# SCH_NFC-Business-Card_new_2024-07-29.net
KiCad netlist of a schematic drawn in EasyEDA
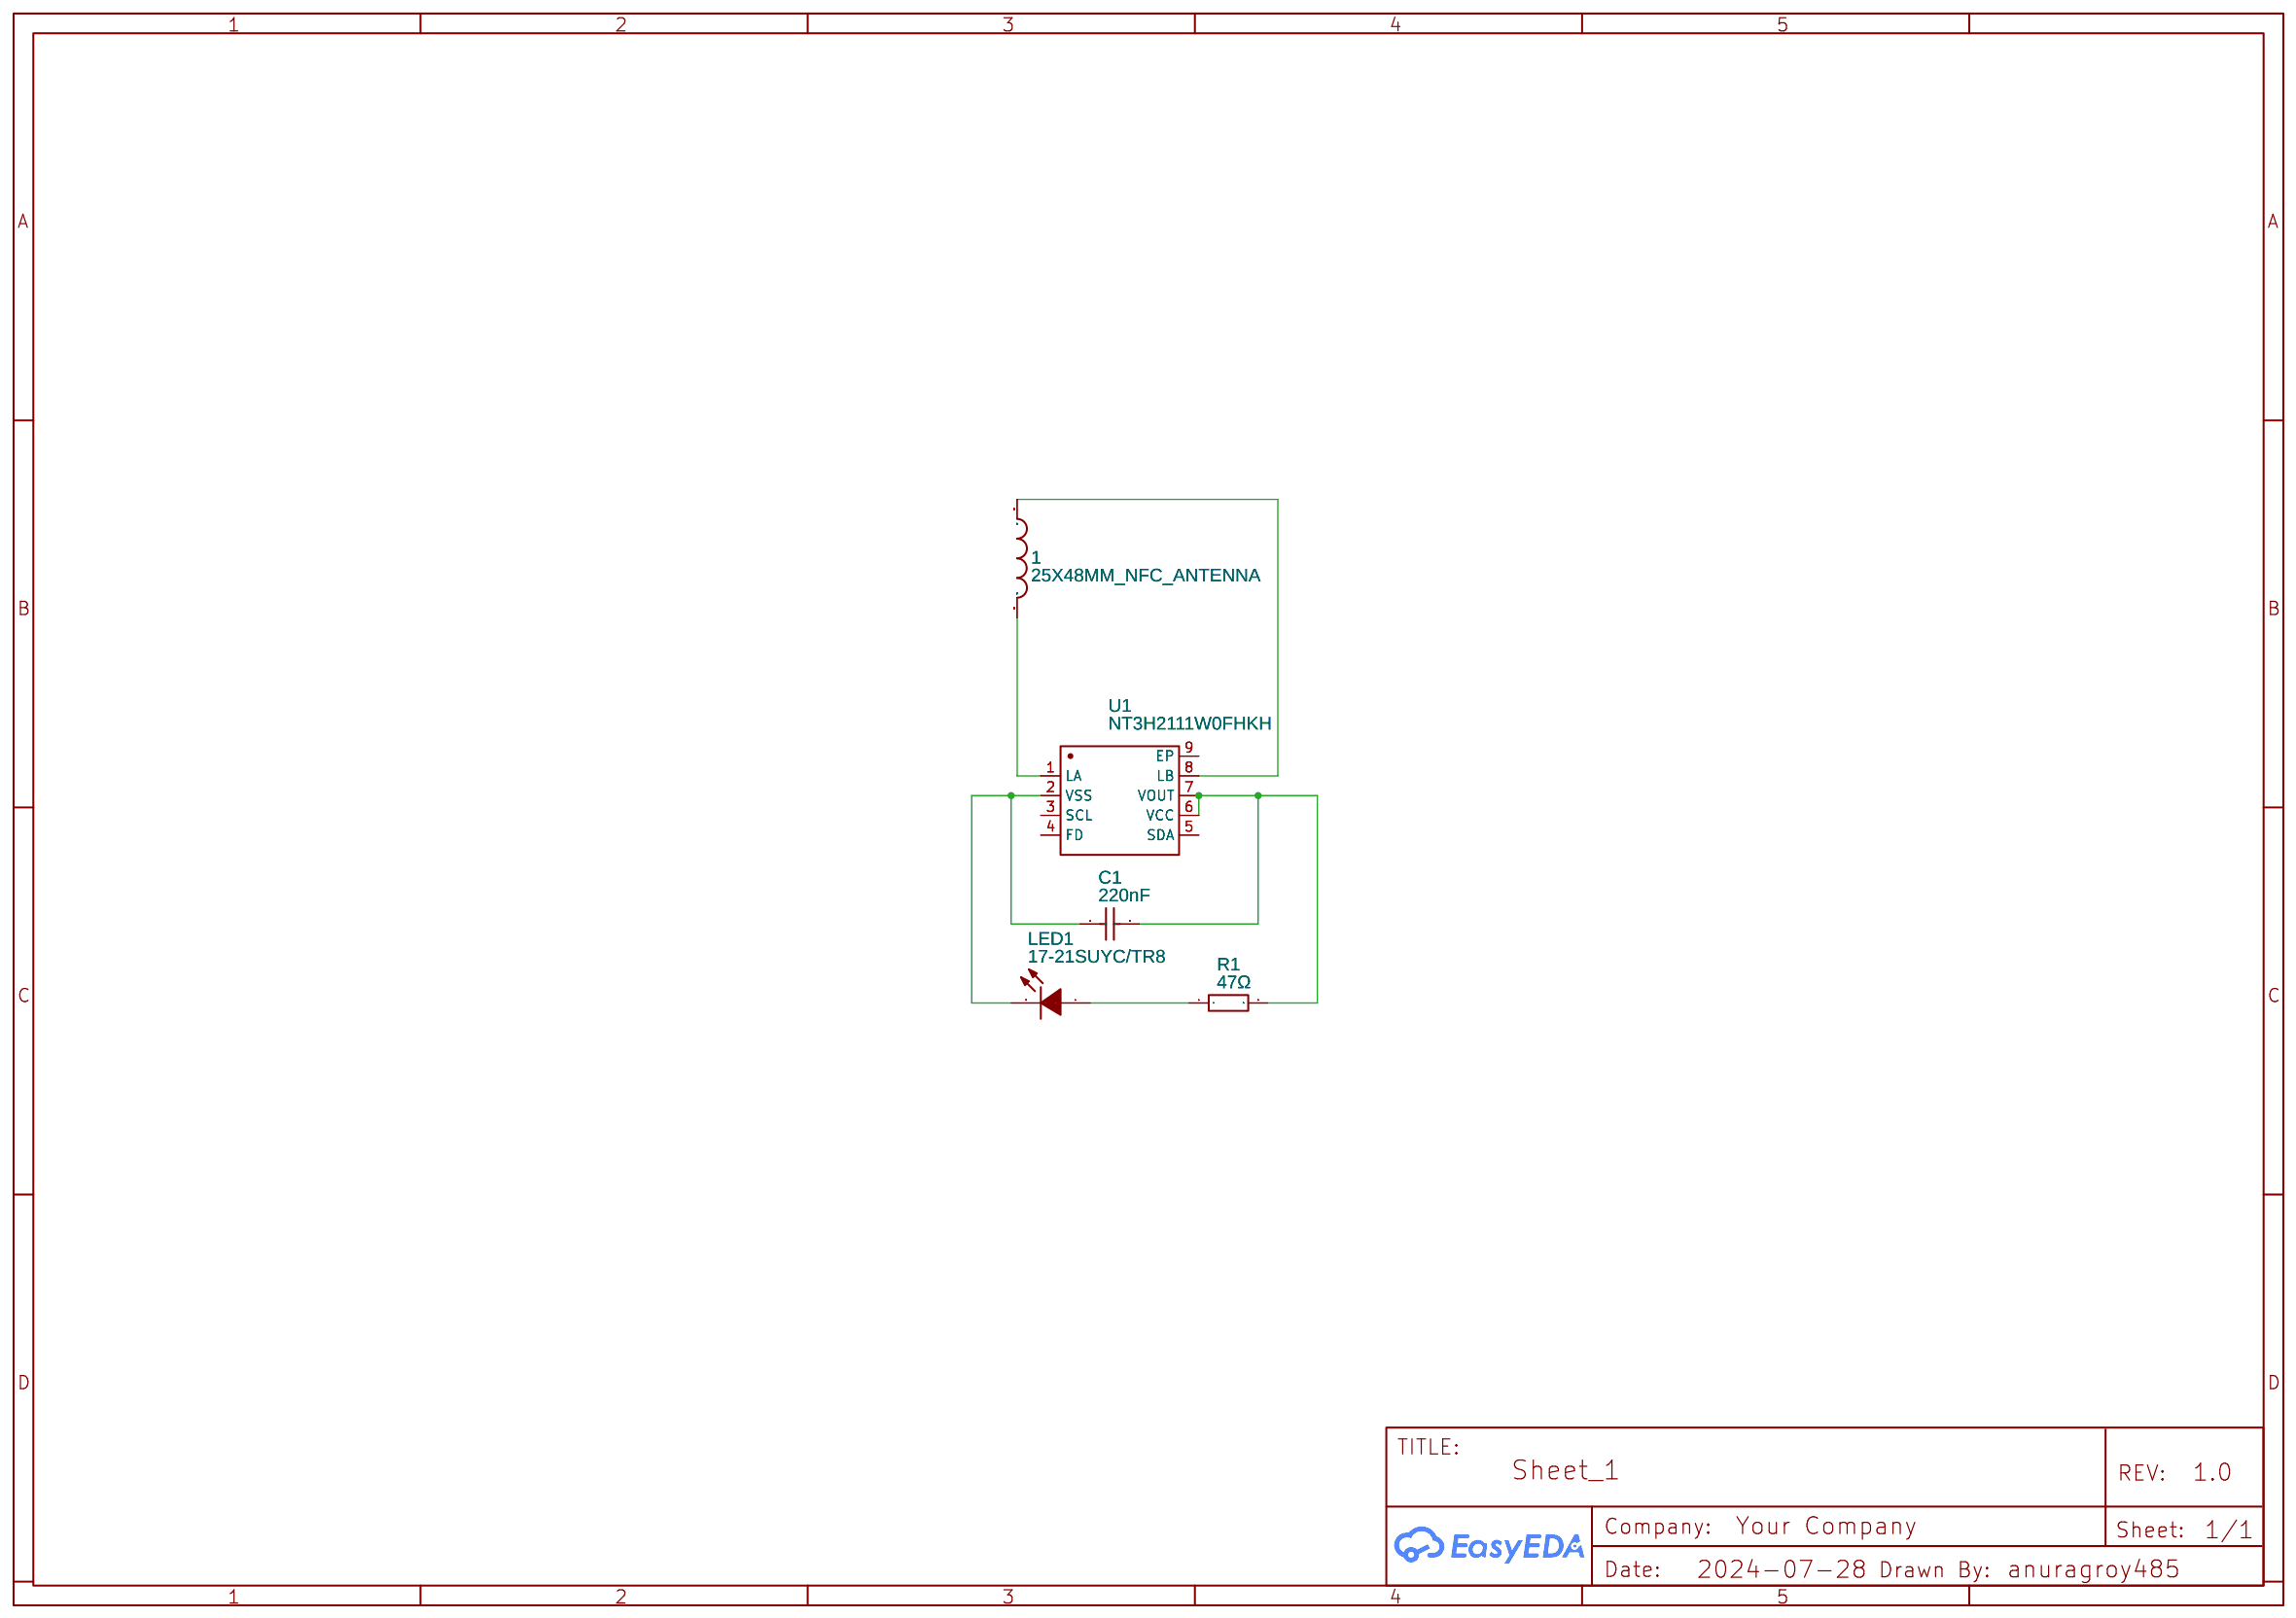
[diagram p0: schematic sheet]

(export (version "E")
  (design (tool "Eeschema 10.0.6"))
  (components
    (comp (ref "1") (value "25X48MM_NFC_ANTENNA") (libsource (lib "") (part "25X48MM_NFC_ANTENNA")))
    (comp (ref "C1")
      (value "220nF")
      (fields
        (field (name "Manufacturer Part") "CL10B224KA8NNNC")
        (field (name "Manufacturer") "SAMSUNG(三星)")
      )
      (libsource (lib "") (part "CL10B224KA8NNNC"))
    )
    (comp (ref "LED1")
      (value "17-21SUYC/TR8")
      (fields (field (name "Manufacturer Part") "KT-0805黄灯") (field (name "Manufacturer") "KENTO"))
      (libsource (lib "") (part "17-21SUYC/TR8"))
    )
    (comp (ref "R1")
      (value "47Ω")
      (fields
        (field (name "Manufacturer Part") "0603WAF470JT5E")
        (field (name "Manufacturer") "UNI-ROYAL(厚声)")
      )
      (libsource (lib "") (part "0603WAF470JT5E"))
    )
    (comp (ref "U1")
      (value "NT3H2111W0FHKH")
      (fields (field (name "Manufacturer") "NXP(恩智浦)"))
      (libsource (lib "") (part "NT3H2111W0FHKH"))
    )
  )
  (nets
    (net (code "1") (name "Net-(LED1-+)") (class "Default")
      (node (ref "LED1") (pin "1") (pinfunction "+_1") (pintype "unspecified"))
      (node (ref "R1") (pin "1") (pinfunction "1_1") (pintype "input"))
    )
    (net (code "2") (name "Net-(LED1--)") (class "Default")
      (node (ref "C1") (pin "1") (pinfunction "1_1") (pintype "input"))
      (node (ref "LED1") (pin "2") (pinfunction "-_2") (pintype "unspecified"))
      (node (ref "U1") (pin "2") (pinfunction "VSS_2") (pintype "unspecified"))
    )
    (net (code "3") (name "Net-(U1-LA)") (class "Default")
      (node (ref "1") (pin "P$2") (pinfunction "P$2_P$2") (pintype "bidirectional"))
      (node (ref "U1") (pin "1") (pinfunction "LA_1") (pintype "unspecified"))
    )
    (net (code "4") (name "Net-(U1-LB)") (class "Default")
      (node (ref "1") (pin "P$1") (pinfunction "P$1_P$1") (pintype "bidirectional"))
      (node (ref "U1") (pin "8") (pinfunction "LB_8") (pintype "unspecified"))
    )
    (net (code "5") (name "Net-(U1-VCC)") (class "Default")
      (node (ref "C1") (pin "2") (pinfunction "2_2") (pintype "input"))
      (node (ref "R1") (pin "2") (pinfunction "2_2") (pintype "input"))
      (node (ref "U1") (pin "6") (pinfunction "VCC_6") (pintype "unspecified"))
      (node (ref "U1") (pin "7") (pinfunction "VOUT_7") (pintype "unspecified"))
    )
    (net (code "6") (name "unconnected-(U1-EP-Pad9)") (class "Default")
      (node (ref "U1") (pin "9") (pinfunction "EP_9") (pintype "unspecified"))
    )
    (net (code "7") (name "unconnected-(U1-FD-Pad4)") (class "Default")
      (node (ref "U1") (pin "4") (pinfunction "FD_4") (pintype "unspecified"))
    )
    (net (code "8") (name "unconnected-(U1-SCL-Pad3)") (class "Default")
      (node (ref "U1") (pin "3") (pinfunction "SCL_3") (pintype "unspecified"))
    )
    (net (code "9") (name "unconnected-(U1-SDA-Pad5)") (class "Default")
      (node (ref "U1") (pin "5") (pinfunction "SDA_5") (pintype "unspecified"))
    )
  )
)
